# Splitter.net
KiCad netlist of a schematic drawn in EAGLE
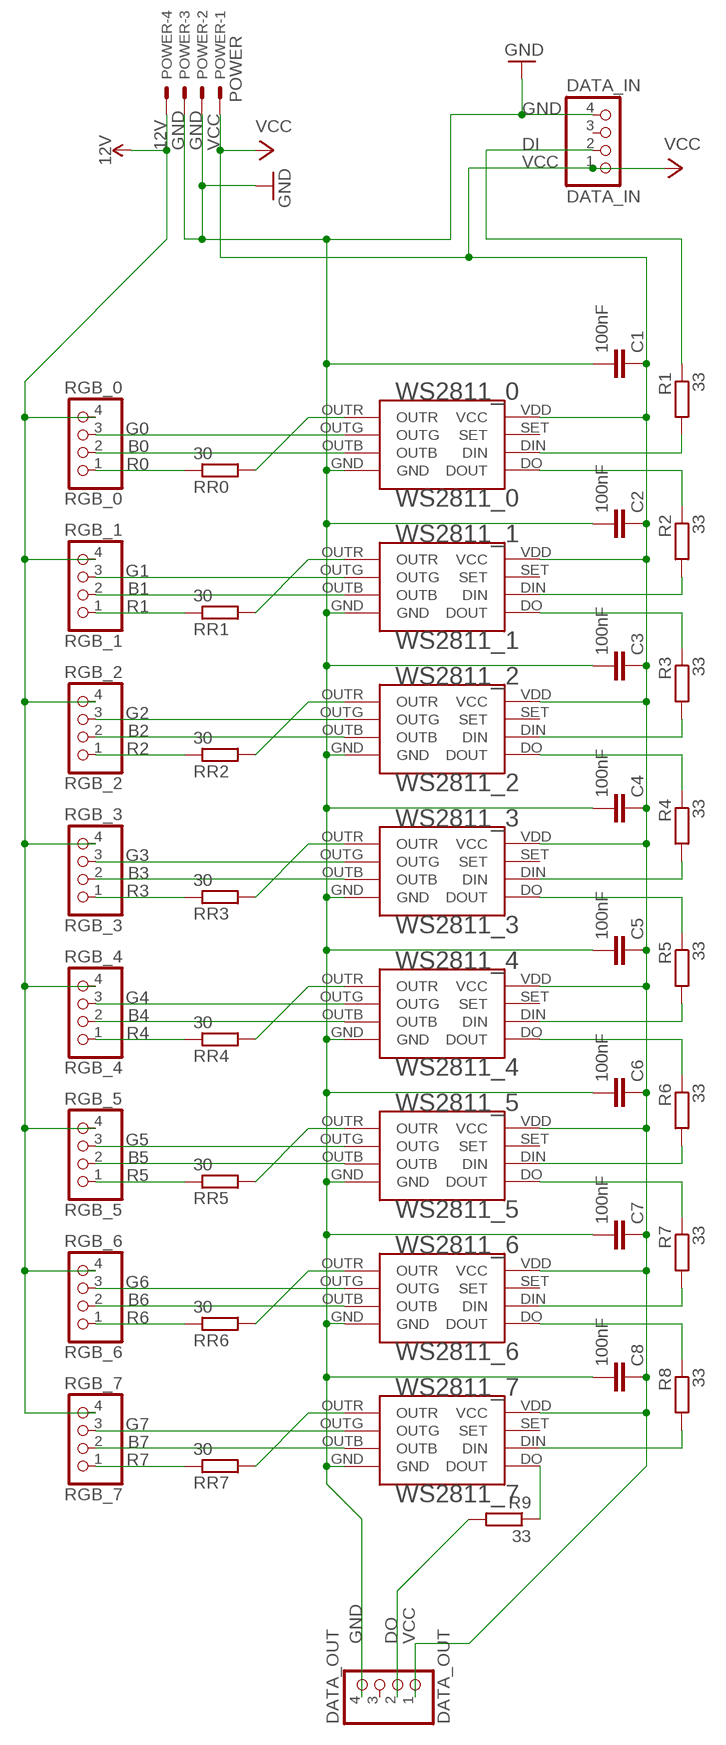
[diagram p0: schematic, sheet 1]

(export (version "E")
  (design (tool "Eeschema 10.0.6"))
  (components
    (comp (ref "C1")
      (value "100nF")
      (footprint "eagle-import:C0805")
      (libsource (lib "eagle-import") (part "C"))
    )
    (comp (ref "C2")
      (value "100nF")
      (footprint "eagle-import:C0805")
      (libsource (lib "eagle-import") (part "C"))
    )
    (comp (ref "C3")
      (value "100nF")
      (footprint "eagle-import:C0805")
      (libsource (lib "eagle-import") (part "C"))
    )
    (comp (ref "C4")
      (value "100nF")
      (footprint "eagle-import:C0805")
      (libsource (lib "eagle-import") (part "C"))
    )
    (comp (ref "C5")
      (value "100nF")
      (footprint "eagle-import:C0805")
      (libsource (lib "eagle-import") (part "C"))
    )
    (comp (ref "C6")
      (value "100nF")
      (footprint "eagle-import:C0805")
      (libsource (lib "eagle-import") (part "C"))
    )
    (comp (ref "C7")
      (value "100nF")
      (footprint "eagle-import:C0805")
      (libsource (lib "eagle-import") (part "C"))
    )
    (comp (ref "C8")
      (value "100nF")
      (footprint "eagle-import:C0805")
      (libsource (lib "eagle-import") (part "C"))
    )
    (comp (ref "DATA_IN")
      (value "DATA_IN")
      (footprint "eagle-import:1X04")
      (libsource (lib "eagle-import") (part "PINHD-1X4"))
    )
    (comp (ref "DATA_OUT")
      (value "DATA_OUT")
      (footprint "eagle-import:1X04")
      (libsource (lib "eagle-import") (part "PINHD-1X4"))
    )
    (comp (ref "POWER")
      (value "POWER")
      (footprint "eagle-import:KK-156-4")
      (fields (field (name "MF") "MOLEX"))
      (libsource (lib "eagle-import") (part "KK-156-4"))
    )
    (comp (ref "R1")
      (value "33")
      (footprint "eagle-import:0204_5")
      (libsource (lib "eagle-import") (part "R-EU_0204/5"))
    )
    (comp (ref "R2")
      (value "33")
      (footprint "eagle-import:0204_5")
      (libsource (lib "eagle-import") (part "R-EU_0204/5"))
    )
    (comp (ref "R3")
      (value "33")
      (footprint "eagle-import:0204_5")
      (libsource (lib "eagle-import") (part "R-EU_0204/5"))
    )
    (comp (ref "R4")
      (value "33")
      (footprint "eagle-import:0204_5")
      (libsource (lib "eagle-import") (part "R-EU_0204/5"))
    )
    (comp (ref "R5")
      (value "33")
      (footprint "eagle-import:0204_5")
      (libsource (lib "eagle-import") (part "R-EU_0204/5"))
    )
    (comp (ref "R6")
      (value "33")
      (footprint "eagle-import:0204_5")
      (libsource (lib "eagle-import") (part "R-EU_0204/5"))
    )
    (comp (ref "R7")
      (value "33")
      (footprint "eagle-import:0204_5")
      (libsource (lib "eagle-import") (part "R-EU_0204/5"))
    )
    (comp (ref "R8")
      (value "33")
      (footprint "eagle-import:0204_5")
      (libsource (lib "eagle-import") (part "R-EU_0204/5"))
    )
    (comp (ref "R9")
      (value "33")
      (footprint "eagle-import:0204_5")
      (libsource (lib "eagle-import") (part "R-EU_0204/5"))
    )
    (comp (ref "RGB_0")
      (value "RGB_0")
      (footprint "eagle-import:1X04")
      (libsource (lib "eagle-import") (part "PINHD-1X4"))
    )
    (comp (ref "RGB_1")
      (value "RGB_1")
      (footprint "eagle-import:1X04")
      (libsource (lib "eagle-import") (part "PINHD-1X4"))
    )
    (comp (ref "RGB_2")
      (value "RGB_2")
      (footprint "eagle-import:1X04")
      (libsource (lib "eagle-import") (part "PINHD-1X4"))
    )
    (comp (ref "RGB_3")
      (value "RGB_3")
      (footprint "eagle-import:1X04")
      (libsource (lib "eagle-import") (part "PINHD-1X4"))
    )
    (comp (ref "RGB_4")
      (value "RGB_4")
      (footprint "eagle-import:1X04")
      (libsource (lib "eagle-import") (part "PINHD-1X4"))
    )
    (comp (ref "RGB_5")
      (value "RGB_5")
      (footprint "eagle-import:1X04")
      (libsource (lib "eagle-import") (part "PINHD-1X4"))
    )
    (comp (ref "RGB_6")
      (value "RGB_6")
      (footprint "eagle-import:1X04")
      (libsource (lib "eagle-import") (part "PINHD-1X4"))
    )
    (comp (ref "RGB_7")
      (value "RGB_7")
      (footprint "eagle-import:1X04")
      (libsource (lib "eagle-import") (part "PINHD-1X4"))
    )
    (comp (ref "RR0")
      (value "30")
      (footprint "eagle-import:0204_5")
      (libsource (lib "eagle-import") (part "R-EU_0204/5"))
    )
    (comp (ref "RR1")
      (value "30")
      (footprint "eagle-import:0204_5")
      (libsource (lib "eagle-import") (part "R-EU_0204/5"))
    )
    (comp (ref "RR2")
      (value "30")
      (footprint "eagle-import:0204_5")
      (libsource (lib "eagle-import") (part "R-EU_0204/5"))
    )
    (comp (ref "RR3")
      (value "30")
      (footprint "eagle-import:0204_5")
      (libsource (lib "eagle-import") (part "R-EU_0204/5"))
    )
    (comp (ref "RR4")
      (value "30")
      (footprint "eagle-import:0204_5")
      (libsource (lib "eagle-import") (part "R-EU_0204/5"))
    )
    (comp (ref "RR5")
      (value "30")
      (footprint "eagle-import:0204_5")
      (libsource (lib "eagle-import") (part "R-EU_0204/5"))
    )
    (comp (ref "RR6")
      (value "30")
      (footprint "eagle-import:0204_5")
      (libsource (lib "eagle-import") (part "R-EU_0204/5"))
    )
    (comp (ref "RR7")
      (value "30")
      (footprint "eagle-import:0204_5")
      (libsource (lib "eagle-import") (part "R-EU_0204/5"))
    )
    (comp (ref "WS2811_0")
      (value "WS2811_0")
      (footprint "eagle-import:WS2811")
      (libsource (lib "eagle-import") (part "WS2811"))
    )
    (comp (ref "WS2811_1")
      (value "WS2811_1")
      (footprint "eagle-import:WS2811")
      (libsource (lib "eagle-import") (part "WS2811"))
    )
    (comp (ref "WS2811_2")
      (value "WS2811_2")
      (footprint "eagle-import:WS2811")
      (libsource (lib "eagle-import") (part "WS2811"))
    )
    (comp (ref "WS2811_3")
      (value "WS2811_3")
      (footprint "eagle-import:WS2811")
      (libsource (lib "eagle-import") (part "WS2811"))
    )
    (comp (ref "WS2811_4")
      (value "WS2811_4")
      (footprint "eagle-import:WS2811")
      (libsource (lib "eagle-import") (part "WS2811"))
    )
    (comp (ref "WS2811_5")
      (value "WS2811_5")
      (footprint "eagle-import:WS2811")
      (libsource (lib "eagle-import") (part "WS2811"))
    )
    (comp (ref "WS2811_6")
      (value "WS2811_6")
      (footprint "eagle-import:WS2811")
      (libsource (lib "eagle-import") (part "WS2811"))
    )
    (comp (ref "WS2811_7")
      (value "WS2811_7")
      (footprint "eagle-import:WS2811")
      (libsource (lib "eagle-import") (part "WS2811"))
    )
  )
  (nets
    (net (code "1") (name "/B0") (class "Default")
      (node (ref "RGB_0") (pin "2") (pinfunction "2_2") (pintype "passive"))
      (node (ref "WS2811_0") (pin "OUTB") (pinfunction "OUTB_OUTB") (pintype "output"))
    )
    (net (code "2") (name "/B1") (class "Default")
      (node (ref "RGB_1") (pin "2") (pinfunction "2_2") (pintype "passive"))
      (node (ref "WS2811_1") (pin "OUTB") (pinfunction "OUTB_OUTB") (pintype "output"))
    )
    (net (code "3") (name "/B2") (class "Default")
      (node (ref "RGB_2") (pin "2") (pinfunction "2_2") (pintype "passive"))
      (node (ref "WS2811_2") (pin "OUTB") (pinfunction "OUTB_OUTB") (pintype "output"))
    )
    (net (code "4") (name "/B3") (class "Default")
      (node (ref "RGB_3") (pin "2") (pinfunction "2_2") (pintype "passive"))
      (node (ref "WS2811_3") (pin "OUTB") (pinfunction "OUTB_OUTB") (pintype "output"))
    )
    (net (code "5") (name "/B4") (class "Default")
      (node (ref "RGB_4") (pin "2") (pinfunction "2_2") (pintype "passive"))
      (node (ref "WS2811_4") (pin "OUTB") (pinfunction "OUTB_OUTB") (pintype "output"))
    )
    (net (code "6") (name "/B5") (class "Default")
      (node (ref "RGB_5") (pin "2") (pinfunction "2_2") (pintype "passive"))
      (node (ref "WS2811_5") (pin "OUTB") (pinfunction "OUTB_OUTB") (pintype "output"))
    )
    (net (code "7") (name "/B6") (class "Default")
      (node (ref "RGB_6") (pin "2") (pinfunction "2_2") (pintype "passive"))
      (node (ref "WS2811_6") (pin "OUTB") (pinfunction "OUTB_OUTB") (pintype "output"))
    )
    (net (code "8") (name "/B7") (class "Default")
      (node (ref "RGB_7") (pin "2") (pinfunction "2_2") (pintype "passive"))
      (node (ref "WS2811_7") (pin "OUTB") (pinfunction "OUTB_OUTB") (pintype "output"))
    )
    (net (code "9") (name "/DI") (class "Default")
      (node (ref "DATA_IN") (pin "2") (pinfunction "2_2") (pintype "passive"))
      (node (ref "R1") (pin "1") (pinfunction "1_1") (pintype "passive"))
    )
    (net (code "10") (name "/DO") (class "Default")
      (node (ref "DATA_OUT") (pin "2") (pinfunction "2_2") (pintype "passive"))
      (node (ref "R9") (pin "2") (pinfunction "2_2") (pintype "passive"))
    )
    (net (code "11") (name "/G0") (class "Default")
      (node (ref "RGB_0") (pin "3") (pinfunction "3_3") (pintype "passive"))
      (node (ref "WS2811_0") (pin "OUTG") (pinfunction "OUTG_OUTG") (pintype "output"))
    )
    (net (code "12") (name "/G1") (class "Default")
      (node (ref "RGB_1") (pin "3") (pinfunction "3_3") (pintype "passive"))
      (node (ref "WS2811_1") (pin "OUTG") (pinfunction "OUTG_OUTG") (pintype "output"))
    )
    (net (code "13") (name "/G2") (class "Default")
      (node (ref "RGB_2") (pin "3") (pinfunction "3_3") (pintype "passive"))
      (node (ref "WS2811_2") (pin "OUTG") (pinfunction "OUTG_OUTG") (pintype "output"))
    )
    (net (code "14") (name "/G3") (class "Default")
      (node (ref "RGB_3") (pin "3") (pinfunction "3_3") (pintype "passive"))
      (node (ref "WS2811_3") (pin "OUTG") (pinfunction "OUTG_OUTG") (pintype "output"))
    )
    (net (code "15") (name "/G4") (class "Default")
      (node (ref "RGB_4") (pin "3") (pinfunction "3_3") (pintype "passive"))
      (node (ref "WS2811_4") (pin "OUTG") (pinfunction "OUTG_OUTG") (pintype "output"))
    )
    (net (code "16") (name "/G5") (class "Default")
      (node (ref "RGB_5") (pin "3") (pinfunction "3_3") (pintype "passive"))
      (node (ref "WS2811_5") (pin "OUTG") (pinfunction "OUTG_OUTG") (pintype "output"))
    )
    (net (code "17") (name "/G6") (class "Default")
      (node (ref "RGB_6") (pin "3") (pinfunction "3_3") (pintype "passive"))
      (node (ref "WS2811_6") (pin "OUTG") (pinfunction "OUTG_OUTG") (pintype "output"))
    )
    (net (code "18") (name "/G7") (class "Default")
      (node (ref "RGB_7") (pin "3") (pinfunction "3_3") (pintype "passive"))
      (node (ref "WS2811_7") (pin "OUTG") (pinfunction "OUTG_OUTG") (pintype "output"))
    )
    (net (code "19") (name "/R0") (class "Default")
      (node (ref "RGB_0") (pin "1") (pinfunction "1_1") (pintype "passive"))
      (node (ref "RR0") (pin "1") (pinfunction "1_1") (pintype "passive"))
    )
    (net (code "20") (name "/R1") (class "Default")
      (node (ref "RGB_1") (pin "1") (pinfunction "1_1") (pintype "passive"))
      (node (ref "RR1") (pin "1") (pinfunction "1_1") (pintype "passive"))
    )
    (net (code "21") (name "/R2") (class "Default")
      (node (ref "RGB_2") (pin "1") (pinfunction "1_1") (pintype "passive"))
      (node (ref "RR2") (pin "1") (pinfunction "1_1") (pintype "passive"))
    )
    (net (code "22") (name "/R3") (class "Default")
      (node (ref "RGB_3") (pin "1") (pinfunction "1_1") (pintype "passive"))
      (node (ref "RR3") (pin "1") (pinfunction "1_1") (pintype "passive"))
    )
    (net (code "23") (name "/R4") (class "Default")
      (node (ref "RGB_4") (pin "1") (pinfunction "1_1") (pintype "passive"))
      (node (ref "RR4") (pin "1") (pinfunction "1_1") (pintype "passive"))
    )
    (net (code "24") (name "/R5") (class "Default")
      (node (ref "RGB_5") (pin "1") (pinfunction "1_1") (pintype "passive"))
      (node (ref "RR5") (pin "1") (pinfunction "1_1") (pintype "passive"))
    )
    (net (code "25") (name "/R6") (class "Default")
      (node (ref "RGB_6") (pin "1") (pinfunction "1_1") (pintype "passive"))
      (node (ref "RR6") (pin "1") (pinfunction "1_1") (pintype "passive"))
    )
    (net (code "26") (name "/R7") (class "Default")
      (node (ref "RGB_7") (pin "1") (pinfunction "1_1") (pintype "passive"))
      (node (ref "RR7") (pin "1") (pinfunction "1_1") (pintype "passive"))
    )
    (net (code "27") (name "12V") (class "Default")
      (node (ref "POWER") (pin "4") (pinfunction "S_4") (pintype "passive"))
      (node (ref "RGB_0") (pin "4") (pinfunction "4_4") (pintype "passive"))
      (node (ref "RGB_1") (pin "4") (pinfunction "4_4") (pintype "passive"))
      (node (ref "RGB_2") (pin "4") (pinfunction "4_4") (pintype "passive"))
      (node (ref "RGB_3") (pin "4") (pinfunction "4_4") (pintype "passive"))
      (node (ref "RGB_4") (pin "4") (pinfunction "4_4") (pintype "passive"))
      (node (ref "RGB_5") (pin "4") (pinfunction "4_4") (pintype "passive"))
      (node (ref "RGB_6") (pin "4") (pinfunction "4_4") (pintype "passive"))
      (node (ref "RGB_7") (pin "4") (pinfunction "4_4") (pintype "passive"))
    )
    (net (code "28") (name "GND") (class "Default")
      (node (ref "C1") (pin "2") (pinfunction "2_2") (pintype "passive"))
      (node (ref "C2") (pin "2") (pinfunction "2_2") (pintype "passive"))
      (node (ref "C3") (pin "2") (pinfunction "2_2") (pintype "passive"))
      (node (ref "C4") (pin "2") (pinfunction "2_2") (pintype "passive"))
      (node (ref "C5") (pin "2") (pinfunction "2_2") (pintype "passive"))
      (node (ref "C6") (pin "2") (pinfunction "2_2") (pintype "passive"))
      (node (ref "C7") (pin "2") (pinfunction "2_2") (pintype "passive"))
      (node (ref "C8") (pin "2") (pinfunction "2_2") (pintype "passive"))
      (node (ref "DATA_IN") (pin "4") (pinfunction "4_4") (pintype "passive"))
      (node (ref "DATA_OUT") (pin "4") (pinfunction "4_4") (pintype "passive"))
      (node (ref "POWER") (pin "2") (pinfunction "S_2") (pintype "passive"))
      (node (ref "POWER") (pin "3") (pinfunction "S_3") (pintype "passive"))
      (node (ref "WS2811_0") (pin "GND") (pinfunction "GND_GND") (pintype "power_in"))
      (node (ref "WS2811_1") (pin "GND") (pinfunction "GND_GND") (pintype "power_in"))
      (node (ref "WS2811_2") (pin "GND") (pinfunction "GND_GND") (pintype "power_in"))
      (node (ref "WS2811_3") (pin "GND") (pinfunction "GND_GND") (pintype "power_in"))
      (node (ref "WS2811_4") (pin "GND") (pinfunction "GND_GND") (pintype "power_in"))
      (node (ref "WS2811_5") (pin "GND") (pinfunction "GND_GND") (pintype "power_in"))
      (node (ref "WS2811_6") (pin "GND") (pinfunction "GND_GND") (pintype "power_in"))
      (node (ref "WS2811_7") (pin "GND") (pinfunction "GND_GND") (pintype "power_in"))
    )
    (net (code "29") (name "Net-(R1-Pad2)") (class "Default")
      (node (ref "R1") (pin "2") (pinfunction "2_2") (pintype "passive"))
      (node (ref "WS2811_0") (pin "DIN") (pinfunction "DIN_DIN") (pintype "input"))
    )
    (net (code "30") (name "Net-(R2-Pad2)") (class "Default")
      (node (ref "R2") (pin "2") (pinfunction "2_2") (pintype "passive"))
      (node (ref "WS2811_1") (pin "DIN") (pinfunction "DIN_DIN") (pintype "input"))
    )
    (net (code "31") (name "Net-(R3-Pad2)") (class "Default")
      (node (ref "R3") (pin "2") (pinfunction "2_2") (pintype "passive"))
      (node (ref "WS2811_2") (pin "DIN") (pinfunction "DIN_DIN") (pintype "input"))
    )
    (net (code "32") (name "Net-(R4-Pad2)") (class "Default")
      (node (ref "R4") (pin "2") (pinfunction "2_2") (pintype "passive"))
      (node (ref "WS2811_3") (pin "DIN") (pinfunction "DIN_DIN") (pintype "input"))
    )
    (net (code "33") (name "Net-(R5-Pad2)") (class "Default")
      (node (ref "R5") (pin "2") (pinfunction "2_2") (pintype "passive"))
      (node (ref "WS2811_4") (pin "DIN") (pinfunction "DIN_DIN") (pintype "input"))
    )
    (net (code "34") (name "Net-(R6-Pad2)") (class "Default")
      (node (ref "R6") (pin "2") (pinfunction "2_2") (pintype "passive"))
      (node (ref "WS2811_5") (pin "DIN") (pinfunction "DIN_DIN") (pintype "input"))
    )
    (net (code "35") (name "Net-(R7-Pad2)") (class "Default")
      (node (ref "R7") (pin "2") (pinfunction "2_2") (pintype "passive"))
      (node (ref "WS2811_6") (pin "DIN") (pinfunction "DIN_DIN") (pintype "input"))
    )
    (net (code "36") (name "Net-(R8-Pad2)") (class "Default")
      (node (ref "R8") (pin "2") (pinfunction "2_2") (pintype "passive"))
      (node (ref "WS2811_7") (pin "DIN") (pinfunction "DIN_DIN") (pintype "input"))
    )
    (net (code "37") (name "Net-(RR0-Pad2)") (class "Default")
      (node (ref "RR0") (pin "2") (pinfunction "2_2") (pintype "passive"))
      (node (ref "WS2811_0") (pin "OUTR") (pinfunction "OUTR_OUTR") (pintype "output"))
    )
    (net (code "38") (name "Net-(RR1-Pad2)") (class "Default")
      (node (ref "RR1") (pin "2") (pinfunction "2_2") (pintype "passive"))
      (node (ref "WS2811_1") (pin "OUTR") (pinfunction "OUTR_OUTR") (pintype "output"))
    )
    (net (code "39") (name "Net-(RR2-Pad2)") (class "Default")
      (node (ref "RR2") (pin "2") (pinfunction "2_2") (pintype "passive"))
      (node (ref "WS2811_2") (pin "OUTR") (pinfunction "OUTR_OUTR") (pintype "output"))
    )
    (net (code "40") (name "Net-(RR3-Pad2)") (class "Default")
      (node (ref "RR3") (pin "2") (pinfunction "2_2") (pintype "passive"))
      (node (ref "WS2811_3") (pin "OUTR") (pinfunction "OUTR_OUTR") (pintype "output"))
    )
    (net (code "41") (name "Net-(RR4-Pad2)") (class "Default")
      (node (ref "RR4") (pin "2") (pinfunction "2_2") (pintype "passive"))
      (node (ref "WS2811_4") (pin "OUTR") (pinfunction "OUTR_OUTR") (pintype "output"))
    )
    (net (code "42") (name "Net-(RR5-Pad2)") (class "Default")
      (node (ref "RR5") (pin "2") (pinfunction "2_2") (pintype "passive"))
      (node (ref "WS2811_5") (pin "OUTR") (pinfunction "OUTR_OUTR") (pintype "output"))
    )
    (net (code "43") (name "Net-(RR6-Pad2)") (class "Default")
      (node (ref "RR6") (pin "2") (pinfunction "2_2") (pintype "passive"))
      (node (ref "WS2811_6") (pin "OUTR") (pinfunction "OUTR_OUTR") (pintype "output"))
    )
    (net (code "44") (name "Net-(RR7-Pad2)") (class "Default")
      (node (ref "RR7") (pin "2") (pinfunction "2_2") (pintype "passive"))
      (node (ref "WS2811_7") (pin "OUTR") (pinfunction "OUTR_OUTR") (pintype "output"))
    )
    (net (code "45") (name "Net-(WS2811_0-DOUT)") (class "Default")
      (node (ref "R2") (pin "1") (pinfunction "1_1") (pintype "passive"))
      (node (ref "WS2811_0") (pin "DO") (pinfunction "DOUT_DO") (pintype "output"))
    )
    (net (code "46") (name "Net-(WS2811_1-DOUT)") (class "Default")
      (node (ref "R3") (pin "1") (pinfunction "1_1") (pintype "passive"))
      (node (ref "WS2811_1") (pin "DO") (pinfunction "DOUT_DO") (pintype "output"))
    )
    (net (code "47") (name "Net-(WS2811_2-DOUT)") (class "Default")
      (node (ref "R4") (pin "1") (pinfunction "1_1") (pintype "passive"))
      (node (ref "WS2811_2") (pin "DO") (pinfunction "DOUT_DO") (pintype "output"))
    )
    (net (code "48") (name "Net-(WS2811_3-DOUT)") (class "Default")
      (node (ref "R5") (pin "1") (pinfunction "1_1") (pintype "passive"))
      (node (ref "WS2811_3") (pin "DO") (pinfunction "DOUT_DO") (pintype "output"))
    )
    (net (code "49") (name "Net-(WS2811_4-DOUT)") (class "Default")
      (node (ref "R6") (pin "1") (pinfunction "1_1") (pintype "passive"))
      (node (ref "WS2811_4") (pin "DO") (pinfunction "DOUT_DO") (pintype "output"))
    )
    (net (code "50") (name "Net-(WS2811_5-DOUT)") (class "Default")
      (node (ref "R7") (pin "1") (pinfunction "1_1") (pintype "passive"))
      (node (ref "WS2811_5") (pin "DO") (pinfunction "DOUT_DO") (pintype "output"))
    )
    (net (code "51") (name "Net-(WS2811_6-DOUT)") (class "Default")
      (node (ref "R8") (pin "1") (pinfunction "1_1") (pintype "passive"))
      (node (ref "WS2811_6") (pin "DO") (pinfunction "DOUT_DO") (pintype "output"))
    )
    (net (code "52") (name "Net-(WS2811_7-DOUT)") (class "Default")
      (node (ref "R9") (pin "1") (pinfunction "1_1") (pintype "passive"))
      (node (ref "WS2811_7") (pin "DO") (pinfunction "DOUT_DO") (pintype "output"))
    )
    (net (code "53") (name "VCC") (class "Default")
      (node (ref "C1") (pin "1") (pinfunction "1_1") (pintype "passive"))
      (node (ref "C2") (pin "1") (pinfunction "1_1") (pintype "passive"))
      (node (ref "C3") (pin "1") (pinfunction "1_1") (pintype "passive"))
      (node (ref "C4") (pin "1") (pinfunction "1_1") (pintype "passive"))
      (node (ref "C5") (pin "1") (pinfunction "1_1") (pintype "passive"))
      (node (ref "C6") (pin "1") (pinfunction "1_1") (pintype "passive"))
      (node (ref "C7") (pin "1") (pinfunction "1_1") (pintype "passive"))
      (node (ref "C8") (pin "1") (pinfunction "1_1") (pintype "passive"))
      (node (ref "DATA_IN") (pin "1") (pinfunction "1_1") (pintype "passive"))
      (node (ref "DATA_OUT") (pin "1") (pinfunction "1_1") (pintype "passive"))
      (node (ref "POWER") (pin "1") (pinfunction "S_1") (pintype "passive"))
      (node (ref "WS2811_0") (pin "VDD") (pinfunction "VCC_VDD") (pintype "power_in"))
      (node (ref "WS2811_1") (pin "VDD") (pinfunction "VCC_VDD") (pintype "power_in"))
      (node (ref "WS2811_2") (pin "VDD") (pinfunction "VCC_VDD") (pintype "power_in"))
      (node (ref "WS2811_3") (pin "VDD") (pinfunction "VCC_VDD") (pintype "power_in"))
      (node (ref "WS2811_4") (pin "VDD") (pinfunction "VCC_VDD") (pintype "power_in"))
      (node (ref "WS2811_5") (pin "VDD") (pinfunction "VCC_VDD") (pintype "power_in"))
      (node (ref "WS2811_6") (pin "VDD") (pinfunction "VCC_VDD") (pintype "power_in"))
      (node (ref "WS2811_7") (pin "VDD") (pinfunction "VCC_VDD") (pintype "power_in"))
    )
    (net (code "54") (name "unconnected-(DATA_IN-Pad3)") (class "Default")
      (node (ref "DATA_IN") (pin "3") (pinfunction "3_3") (pintype "passive"))
    )
    (net (code "55") (name "unconnected-(DATA_OUT-Pad3)") (class "Default")
      (node (ref "DATA_OUT") (pin "3") (pinfunction "3_3") (pintype "passive"))
    )
    (net (code "56") (name "unconnected-(WS2811_0-PadSET)") (class "Default")
      (node (ref "WS2811_0") (pin "SET") (pinfunction "SET_SET") (pintype "input"))
    )
    (net (code "57") (name "unconnected-(WS2811_1-PadSET)") (class "Default")
      (node (ref "WS2811_1") (pin "SET") (pinfunction "SET_SET") (pintype "input"))
    )
    (net (code "58") (name "unconnected-(WS2811_2-PadSET)") (class "Default")
      (node (ref "WS2811_2") (pin "SET") (pinfunction "SET_SET") (pintype "input"))
    )
    (net (code "59") (name "unconnected-(WS2811_3-PadSET)") (class "Default")
      (node (ref "WS2811_3") (pin "SET") (pinfunction "SET_SET") (pintype "input"))
    )
    (net (code "60") (name "unconnected-(WS2811_4-PadSET)") (class "Default")
      (node (ref "WS2811_4") (pin "SET") (pinfunction "SET_SET") (pintype "input"))
    )
    (net (code "61") (name "unconnected-(WS2811_5-PadSET)") (class "Default")
      (node (ref "WS2811_5") (pin "SET") (pinfunction "SET_SET") (pintype "input"))
    )
    (net (code "62") (name "unconnected-(WS2811_6-PadSET)") (class "Default")
      (node (ref "WS2811_6") (pin "SET") (pinfunction "SET_SET") (pintype "input"))
    )
    (net (code "63") (name "unconnected-(WS2811_7-PadSET)") (class "Default")
      (node (ref "WS2811_7") (pin "SET") (pinfunction "SET_SET") (pintype "input"))
    )
  )
)
